# Cellular.net
KiCad netlist of a schematic drawn in Altium Designer
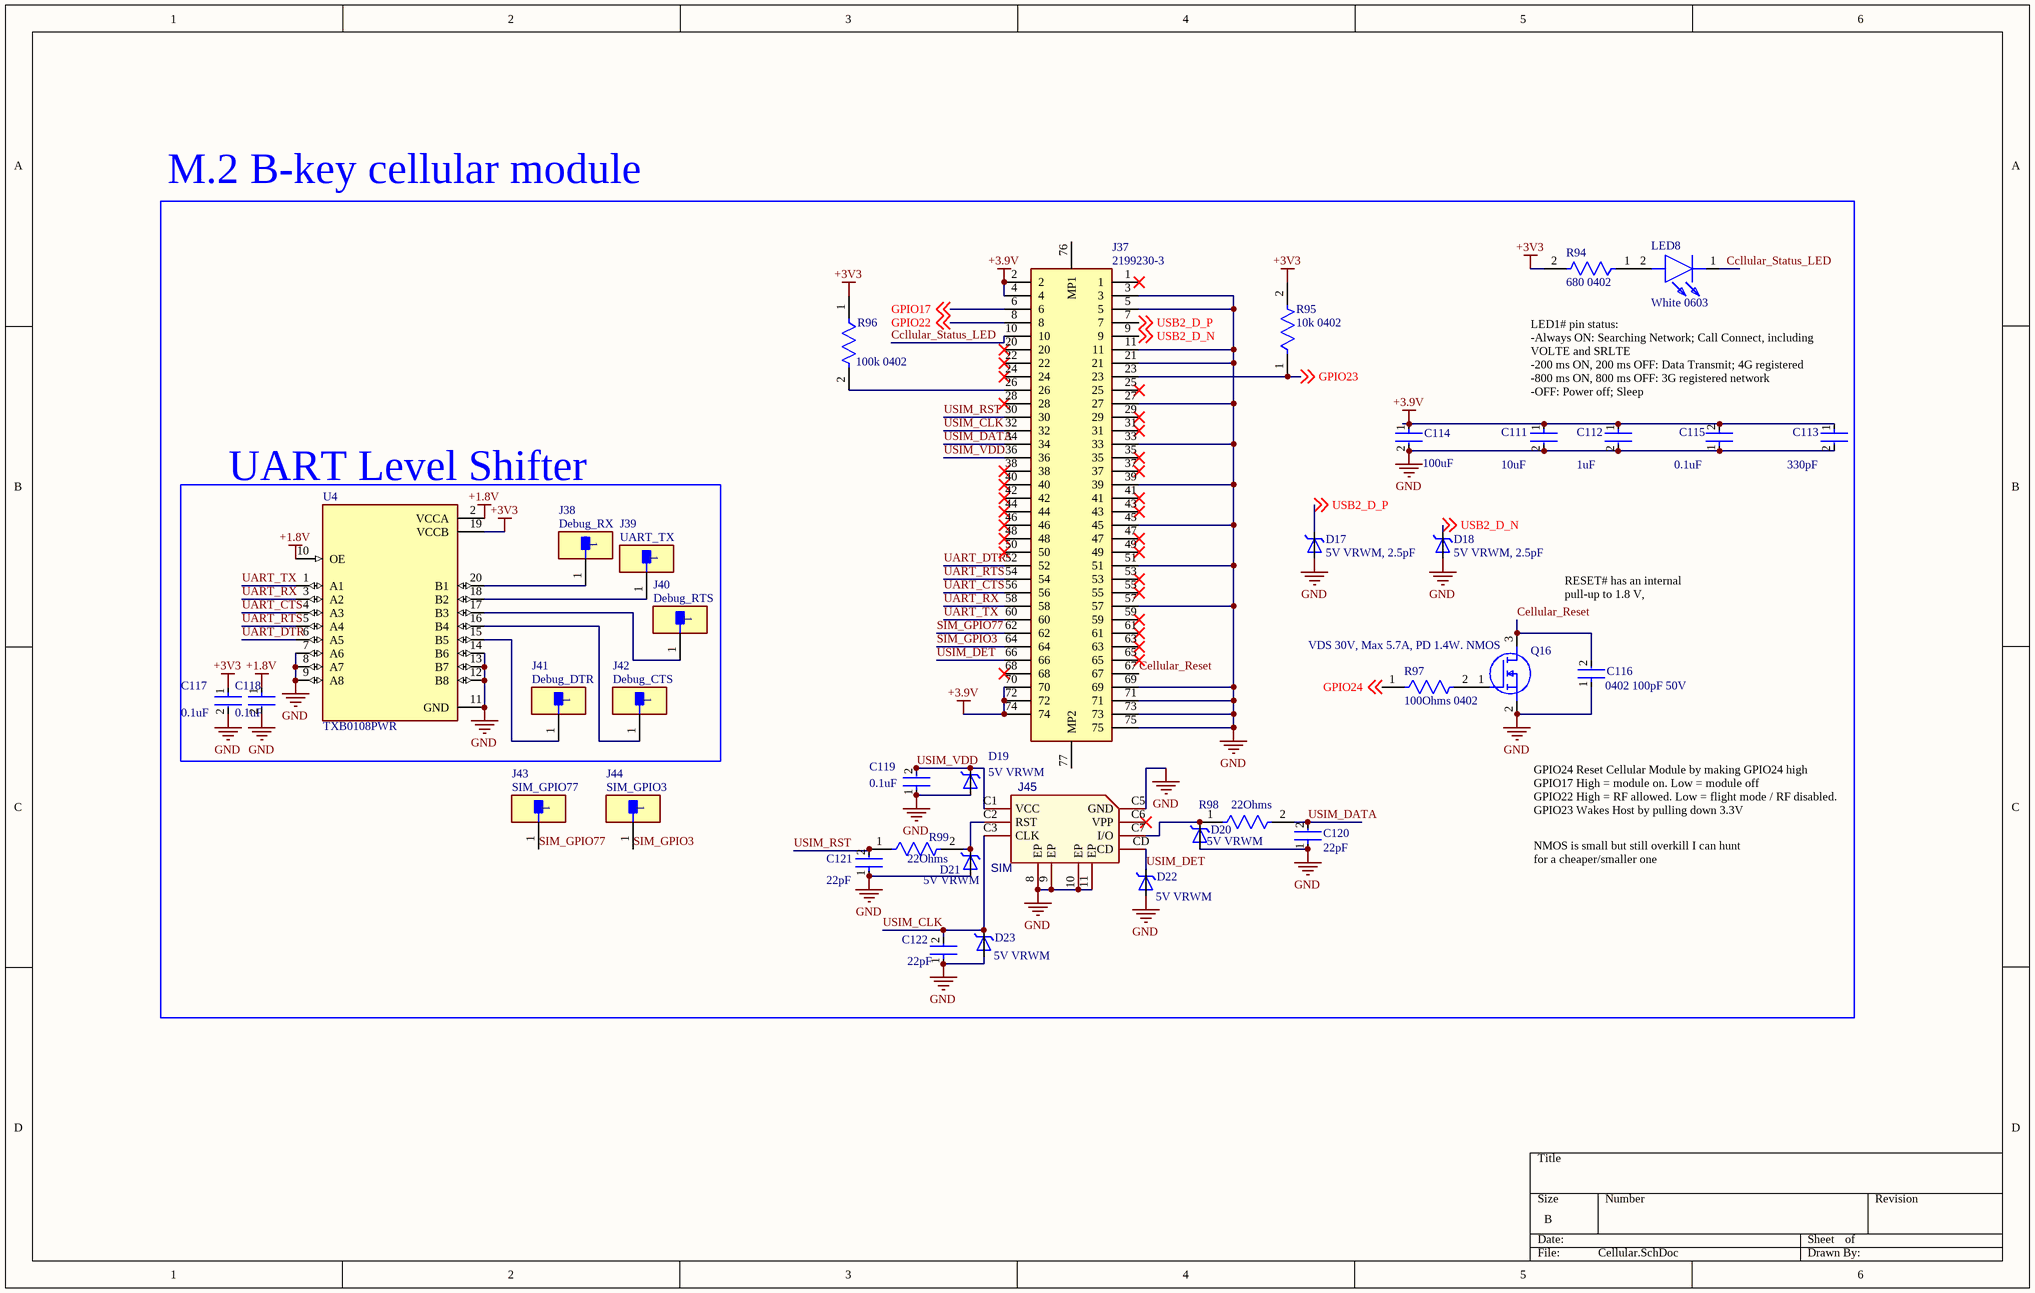
[diagram p0: Cellular.SchDoc]

(export (version "E")
  (design (tool "Eeschema 10.0.6"))
  (components
    (comp (ref "C111")
      (value "10uF")
      (footprint "FP-CC0603-DC-MFG")
      (description "C96446")
      (fields (field (name "TOLERANCE") "10%"))
      (libsource (lib "Altium Content Vault") (part "b4654b650e69147ec39a6b967a45e02"))
    )
    (comp (ref "C112")
      (value "1uF")
      (footprint "FP-C0402-BB-MFG")
      (description "C52923")
      (fields
        (field (name "TOLERANCE") "0.2")
        (field (name "OCTOPART") "https://octopart.com/c0402c104m3pac7867-kemet-84304880")
      )
      (libsource (lib "Altium Content Vault") (part "b4654b650e69147ec39a6b967a45e02"))
    )
    (comp (ref "C113")
      (value "330pF")
      (footprint "FP-C0402-BB-MFG")
      (description "C13533")
      (fields
        (field (name "TOLERANCE") "0.2")
        (field (name "OCTOPART") "https://octopart.com/c0402c104m3pac7867-kemet-84304880")
      )
      (libsource (lib "Altium Content Vault") (part "b4654b650e69147ec39a6b967a45e02"))
    )
    (comp (ref "C114")
      (value "100uF")
      (footprint "FP-CC1210-GD-IPC_A")
      (description "C7432790")
      (fields (field (name "TOLERANCE") "20%"))
      (libsource (lib "Altium Content Vault") (part "b4654b650e69147ec39a6b967a45e02"))
    )
    (comp (ref "C115")
      (value "0.1uF")
      (footprint "FP-C0402-BB-MFG")
      (description "C307331")
      (fields
        (field (name "TOLERANCE") "0.2")
        (field (name "OCTOPART") "https://octopart.com/c0402c104m3pac7867-kemet-84304880")
      )
      (libsource (lib "Altium Content Vault") (part "b4654b650e69147ec39a6b967a45e02"))
    )
    (comp (ref "C116")
      (value "0402 100pF 50V")
      (footprint "FP-C0402-BB-MFG")
      (description "C1546")
      (fields
        (field (name "TOLERANCE") "0.2")
        (field (name "OCTOPART") "https://octopart.com/c0402c104m3pac7867-kemet-84304880")
      )
      (libsource (lib "Altium Content Vault") (part "b4654b650e69147ec39a6b967a45e02"))
    )
    (comp (ref "C117")
      (value "0.1uF")
      (footprint "FP-C0402-BB-MFG")
      (description "C307331")
      (fields
        (field (name "TOLERANCE") "0.2")
        (field (name "OCTOPART") "https://octopart.com/c0402c104m3pac7867-kemet-84304880")
      )
      (libsource (lib "Altium Content Vault") (part "b4654b650e69147ec39a6b967a45e02"))
    )
    (comp (ref "C118")
      (value "0.1uF")
      (footprint "FP-C0402-BB-MFG")
      (description "C307331")
      (fields
        (field (name "TOLERANCE") "0.2")
        (field (name "OCTOPART") "https://octopart.com/c0402c104m3pac7867-kemet-84304880")
      )
      (libsource (lib "Altium Content Vault") (part "b4654b650e69147ec39a6b967a45e02"))
    )
    (comp (ref "C119")
      (value "0.1uF")
      (footprint "FP-C0402-BB-MFG")
      (description "C307331")
      (fields
        (field (name "TOLERANCE") "0.2")
        (field (name "OCTOPART") "https://octopart.com/c0402c104m3pac7867-kemet-84304880")
      )
      (libsource (lib "Altium Content Vault") (part "b4654b650e69147ec39a6b967a45e02"))
    )
    (comp (ref "C120")
      (value "22pF")
      (footprint "FP-C0402-BB-MFG")
      (description "C1555")
      (fields
        (field (name "TOLERANCE") "0.2")
        (field (name "OCTOPART") "https://octopart.com/c0402c104m3pac7867-kemet-84304880")
      )
      (libsource (lib "Altium Content Vault") (part "b4654b650e69147ec39a6b967a45e02"))
    )
    (comp (ref "C121")
      (value "22pF")
      (footprint "FP-C0402-BB-MFG")
      (description "C1555")
      (fields
        (field (name "TOLERANCE") "0.2")
        (field (name "OCTOPART") "https://octopart.com/c0402c104m3pac7867-kemet-84304880")
      )
      (libsource (lib "Altium Content Vault") (part "b4654b650e69147ec39a6b967a45e02"))
    )
    (comp (ref "C122")
      (value "22pF")
      (footprint "FP-C0402-BB-MFG")
      (description "C1555")
      (fields
        (field (name "TOLERANCE") "0.2")
        (field (name "OCTOPART") "https://octopart.com/c0402c104m3pac7867-kemet-84304880")
      )
      (libsource (lib "Altium Content Vault") (part "b4654b650e69147ec39a6b967a45e02"))
    )
    (comp (ref "D17")
      (value "5V VRWM, 2.5pF")
      (footprint "PcbLib1:SODFL1060X40N")
      (description "C242267")
      (fields (field (name "MF") "ON Semiconductor") (field (name "MP") "ESD9M5.0ST5G"))
      (libsource (lib "Schlib1") (part "ESD9M5.0ST5G"))
    )
    (comp (ref "D18")
      (value "5V VRWM, 2.5pF")
      (footprint "PcbLib1:SODFL1060X40N")
      (description "C242267")
      (fields (field (name "MF") "ON Semiconductor") (field (name "MP") "ESD9M5.0ST5G"))
      (libsource (lib "Schlib1") (part "ESD9M5.0ST5G"))
    )
    (comp (ref "D19")
      (value "5V VRWM")
      (footprint "PcbLib1:SODFL1060X40N")
      (description "C242267")
      (fields (field (name "MF") "ON Semiconductor") (field (name "MP") "ESD9M5.0ST5G"))
      (libsource (lib "Schlib1") (part "ESD9M5.0ST5G"))
    )
    (comp (ref "D20")
      (value "5V VRWM")
      (footprint "PcbLib1:SODFL1060X40N")
      (description "C242267")
      (fields (field (name "MF") "ON Semiconductor") (field (name "MP") "ESD9M5.0ST5G"))
      (libsource (lib "Schlib1") (part "ESD9M5.0ST5G"))
    )
    (comp (ref "D21")
      (value "5V VRWM")
      (footprint "PcbLib1:SODFL1060X40N")
      (description "C242267")
      (fields (field (name "MF") "ON Semiconductor") (field (name "MP") "ESD9M5.0ST5G"))
      (libsource (lib "Schlib1") (part "ESD9M5.0ST5G"))
    )
    (comp (ref "D22")
      (value "5V VRWM")
      (footprint "PcbLib1:SODFL1060X40N")
      (description "C242267")
      (fields (field (name "MF") "ON Semiconductor") (field (name "MP") "ESD9M5.0ST5G"))
      (libsource (lib "Schlib1") (part "ESD9M5.0ST5G"))
    )
    (comp (ref "D23")
      (value "5V VRWM")
      (footprint "PcbLib1:SODFL1060X40N")
      (description "C242267")
      (fields (field (name "MF") "ON Semiconductor") (field (name "MP") "ESD9M5.0ST5G"))
      (libsource (lib "Schlib1") (part "ESD9M5.0ST5G"))
    )
    (comp (ref "J37")
      (value "2199230-3")
      (footprint "PcbLib1:21992303")
      (description "C590859")
      (fields (field (name "MOUSER PART NUMBER") "571-2199230-3"))
      (libsource (lib "*") (part "2199230-3"))
    )
    (comp (ref "J38")
      (value "Debug_RX")
      (footprint "FP-5015-MFG")
      (description "PC TEST POINT MINIATURE")
      (fields (field (name "MANUFACTURER PART NUMBER") "5015") (field (name "MANUFACTURER") "keystone"))
      (libsource (lib "Altium Content Vault") (part "dd45045ce8184df9e99e12baf3f412c"))
    )
    (comp (ref "J39")
      (value "UART_TX")
      (footprint "FP-5015-MFG")
      (description "PC TEST POINT MINIATURE")
      (fields (field (name "MANUFACTURER PART NUMBER") "5015") (field (name "MANUFACTURER") "keystone"))
      (libsource (lib "Altium Content Vault") (part "dd45045ce8184df9e99e12baf3f412c"))
    )
    (comp (ref "J40")
      (value "Debug_RTS")
      (footprint "FP-5015-MFG")
      (description "PC TEST POINT MINIATURE")
      (fields (field (name "MANUFACTURER PART NUMBER") "5015") (field (name "MANUFACTURER") "keystone"))
      (libsource (lib "Altium Content Vault") (part "dd45045ce8184df9e99e12baf3f412c"))
    )
    (comp (ref "J41")
      (value "Debug_DTR")
      (footprint "FP-5015-MFG")
      (description "PC TEST POINT MINIATURE")
      (fields (field (name "MANUFACTURER PART NUMBER") "5015") (field (name "MANUFACTURER") "keystone"))
      (libsource (lib "Altium Content Vault") (part "dd45045ce8184df9e99e12baf3f412c"))
    )
    (comp (ref "J42")
      (value "Debug_CTS")
      (footprint "FP-5015-MFG")
      (description "PC TEST POINT MINIATURE")
      (fields (field (name "MANUFACTURER PART NUMBER") "5015") (field (name "MANUFACTURER") "keystone"))
      (libsource (lib "Altium Content Vault") (part "dd45045ce8184df9e99e12baf3f412c"))
    )
    (comp (ref "J43")
      (value "SIM_GPIO77")
      (footprint "FP-5015-MFG")
      (description "PC TEST POINT MINIATURE")
      (fields (field (name "MANUFACTURER PART NUMBER") "5015") (field (name "MANUFACTURER") "keystone"))
      (libsource (lib "Altium Content Vault") (part "dd45045ce8184df9e99e12baf3f412c"))
    )
    (comp (ref "J44")
      (value "SIM_GPIO3")
      (footprint "FP-5015-MFG")
      (description "PC TEST POINT MINIATURE")
      (fields (field (name "MANUFACTURER PART NUMBER") "5015") (field (name "MANUFACTURER") "keystone"))
      (libsource (lib "Altium Content Vault") (part "dd45045ce8184df9e99e12baf3f412c"))
    )
    (comp (ref "J45")
      (value "SIM")
      (footprint "PCBComponent_1")
      (description "C266888")
      (fields (field (name "MANUFACTURER") "XUNPU(讯普)") (field (name "MANUFACTURER PART") "SMN-303"))
      (libsource (lib "Schlib1") (part "SMN-303"))
    )
    (comp (ref "LED8")
      (value "White 0603")
      (footprint "SamacSys:LEDC1608X70N")
      (description "C2290")
      (fields (field (name "MANUFACTURER_PART_NUMBER") "KT-0603R"))
      (libsource (lib "*") (part "KT-0603R"))
    )
    (comp (ref "Q16")
      (value "VDS 30V, Max 5.7A, PD 1.4W. NMOS")
      (footprint "PcbLib1:SOT95P280X125-3N")
      (description "C20917")
      (fields (field (name "MANUFACTURER_PART_NUMBER") "AO3400A"))
      (libsource (lib "*") (part "AO3400A"))
    )
    (comp (ref "R94")
      (value "680 0402")
      (footprint "FP-AF0402-IPC_B")
      (description "C2835749")
      (fields (field (name "TOLERANCE") "5%"))
      (libsource (lib "Altium Content Vault") (part "1029c3af85768c4190bb7ad29bc67b5"))
    )
    (comp (ref "R95")
      (value "10k 0402")
      (footprint "FP-RMCF0402-MFG")
      (description "C25744")
      (fields (field (name "TOLERANCE") "5%"))
      (libsource (lib "Altium Content Vault") (part "1029c3af85768c4190bb7ad29bc67b5"))
    )
    (comp (ref "R96")
      (value "100k 0402")
      (footprint "FP-RMCF0402-MFG")
      (description "C25741")
      (fields (field (name "TOLERANCE") "5%"))
      (libsource (lib "Altium Content Vault") (part "1029c3af85768c4190bb7ad29bc67b5"))
    )
    (comp (ref "R97")
      (value "100Ohms 0402")
      (footprint "FP-RMCF0402-MFG")
      (description "C25076")
      (fields (field (name "TOLERANCE") "5%"))
      (libsource (lib "Altium Content Vault") (part "1029c3af85768c4190bb7ad29bc67b5"))
    )
    (comp (ref "R98")
      (value "22Ohms")
      (footprint "FP-RMCF0402-MFG")
      (description "C25092")
      (fields (field (name "TOLERANCE") "5%"))
      (libsource (lib "Altium Content Vault") (part "1029c3af85768c4190bb7ad29bc67b5"))
    )
    (comp (ref "R99")
      (value "22Ohms")
      (footprint "FP-RMCF0402-MFG")
      (description "C25092")
      (fields (field (name "TOLERANCE") "5%"))
      (libsource (lib "Altium Content Vault") (part "1029c3af85768c4190bb7ad29bc67b5"))
    )
    (comp (ref "U4")
      (value "TXB0108PWR")
      (footprint "SOP65P640X120-20N")
      (description "C53406")
      (fields (field (name "MF") "Texas Instruments") (field (name "DIGI-KEY_PART_NUMBER") "296-21527-2-ND"))
      (libsource (lib "Schlib1") (part "TXB0108PWR"))
    )
  )
  (nets
    (net (code "1") (name "+1.8V") (class "Default")
      (node (ref "C118") (pin "1") (pinfunction "1_1") (pintype "passive"))
      (node (ref "U4") (pin "10") (pinfunction "OE_10") (pintype "input"))
      (node (ref "U4") (pin "2") (pinfunction "VCCA_2") (pintype "power_in"))
    )
    (net (code "2") (name "+3.9V") (class "Default")
      (node (ref "C111") (pin "1") (pinfunction "1_1") (pintype "passive"))
      (node (ref "C112") (pin "1") (pinfunction "1_1") (pintype "passive"))
      (node (ref "C113") (pin "1") (pinfunction "1_1") (pintype "passive"))
      (node (ref "C114") (pin "1") (pinfunction "1_1") (pintype "passive"))
      (node (ref "C115") (pin "2") (pinfunction "2_2") (pintype "passive"))
      (node (ref "J37") (pin "2") (pinfunction "2_2") (pintype "passive"))
      (node (ref "J37") (pin "4") (pinfunction "4_4") (pintype "passive"))
      (node (ref "J37") (pin "70") (pinfunction "70_70") (pintype "passive"))
      (node (ref "J37") (pin "72") (pinfunction "72_72") (pintype "passive"))
      (node (ref "J37") (pin "74") (pinfunction "74_74") (pintype "passive"))
    )
    (net (code "3") (name "+3V3") (class "Default")
      (node (ref "C117") (pin "1") (pinfunction "1_1") (pintype "passive"))
      (node (ref "R94") (pin "2") (pinfunction "2_2") (pintype "passive"))
      (node (ref "R95") (pin "2") (pinfunction "2_2") (pintype "passive"))
      (node (ref "R96") (pin "1") (pinfunction "1_1") (pintype "passive"))
      (node (ref "U4") (pin "19") (pinfunction "VCCB_19") (pintype "power_in"))
    )
    (net (code "4") (name "/Ccllular_Status_LED") (class "Default")
      (node (ref "J37") (pin "10") (pinfunction "10_10") (pintype "passive"))
      (node (ref "LED8") (pin "1") (pinfunction "K_1") (pintype "passive"))
    )
    (net (code "5") (name "/Cellular_Reset") (class "Default")
      (node (ref "C116") (pin "2") (pinfunction "2_2") (pintype "passive"))
      (node (ref "J37") (pin "67") (pinfunction "67_67") (pintype "passive"))
      (node (ref "Q16") (pin "3") (pinfunction "D_3") (pintype "passive"))
    )
    (net (code "6") (name "/SIM_GPIO3") (class "Default")
      (node (ref "J37") (pin "64") (pinfunction "64_64") (pintype "passive"))
      (node (ref "J44") (pin "1") (pinfunction "1_1") (pintype "passive"))
    )
    (net (code "7") (name "/SIM_GPIO77") (class "Default")
      (node (ref "J37") (pin "62") (pinfunction "62_62") (pintype "passive"))
      (node (ref "J43") (pin "1") (pinfunction "1_1") (pintype "passive"))
    )
    (net (code "8") (name "/UART_CTS") (class "Default")
      (node (ref "J37") (pin "56") (pinfunction "56_56") (pintype "passive"))
      (node (ref "U4") (pin "4") (pinfunction "A3_4") (pintype "bidirectional"))
    )
    (net (code "9") (name "/UART_DTR") (class "Default")
      (node (ref "J37") (pin "52") (pinfunction "52_52") (pintype "passive"))
      (node (ref "U4") (pin "6") (pinfunction "A5_6") (pintype "bidirectional"))
    )
    (net (code "10") (name "/UART_RTS") (class "Default")
      (node (ref "J37") (pin "54") (pinfunction "54_54") (pintype "passive"))
      (node (ref "U4") (pin "5") (pinfunction "A4_5") (pintype "bidirectional"))
    )
    (net (code "11") (name "/UART_RX") (class "Default")
      (node (ref "J37") (pin "58") (pinfunction "58_58") (pintype "passive"))
      (node (ref "U4") (pin "3") (pinfunction "A2_3") (pintype "bidirectional"))
    )
    (net (code "12") (name "/UART_TX") (class "Default")
      (node (ref "J37") (pin "60") (pinfunction "60_60") (pintype "passive"))
      (node (ref "U4") (pin "1") (pinfunction "A1_1") (pintype "bidirectional"))
    )
    (net (code "13") (name "/USIM_CLK") (class "Default")
      (node (ref "C122") (pin "2") (pinfunction "2_2") (pintype "passive"))
      (node (ref "D23") (pin "1") (pinfunction "1_1") (pintype "passive"))
      (node (ref "J37") (pin "32") (pinfunction "32_32") (pintype "passive"))
      (node (ref "J45") (pin "C3") (pinfunction "CLK_C3") (pintype "passive"))
    )
    (net (code "14") (name "/USIM_DATA") (class "Default")
      (node (ref "C120") (pin "2") (pinfunction "2_2") (pintype "passive"))
      (node (ref "J37") (pin "34") (pinfunction "34_34") (pintype "passive"))
      (node (ref "R98") (pin "2") (pinfunction "2_2") (pintype "passive"))
    )
    (net (code "15") (name "/USIM_DET") (class "Default")
      (node (ref "D22") (pin "1") (pinfunction "1_1") (pintype "passive"))
      (node (ref "J37") (pin "66") (pinfunction "66_66") (pintype "passive"))
      (node (ref "J45") (pin "CD") (pinfunction "CD_CD") (pintype "passive"))
    )
    (net (code "16") (name "/USIM_RST") (class "Default")
      (node (ref "C121") (pin "2") (pinfunction "2_2") (pintype "passive"))
      (node (ref "J37") (pin "30") (pinfunction "30_30") (pintype "passive"))
      (node (ref "R99") (pin "1") (pinfunction "1_1") (pintype "passive"))
    )
    (net (code "17") (name "/USIM_VDD") (class "Default")
      (node (ref "C119") (pin "2") (pinfunction "2_2") (pintype "passive"))
      (node (ref "D19") (pin "1") (pinfunction "1_1") (pintype "passive"))
      (node (ref "J37") (pin "36") (pinfunction "36_36") (pintype "passive"))
      (node (ref "J45") (pin "C1") (pinfunction "VCC_C1") (pintype "passive"))
    )
    (net (code "18") (name "GND") (class "Default")
      (node (ref "C111") (pin "2") (pinfunction "2_2") (pintype "passive"))
      (node (ref "C112") (pin "2") (pinfunction "2_2") (pintype "passive"))
      (node (ref "C113") (pin "2") (pinfunction "2_2") (pintype "passive"))
      (node (ref "C114") (pin "2") (pinfunction "2_2") (pintype "passive"))
      (node (ref "C115") (pin "1") (pinfunction "1_1") (pintype "passive"))
      (node (ref "C116") (pin "1") (pinfunction "1_1") (pintype "passive"))
      (node (ref "C117") (pin "2") (pinfunction "2_2") (pintype "passive"))
      (node (ref "C118") (pin "2") (pinfunction "2_2") (pintype "passive"))
      (node (ref "C119") (pin "1") (pinfunction "1_1") (pintype "passive"))
      (node (ref "C120") (pin "1") (pinfunction "1_1") (pintype "passive"))
      (node (ref "C121") (pin "1") (pinfunction "1_1") (pintype "passive"))
      (node (ref "C122") (pin "1") (pinfunction "1_1") (pintype "passive"))
      (node (ref "D17") (pin "2") (pinfunction "2_2") (pintype "passive"))
      (node (ref "D18") (pin "2") (pinfunction "2_2") (pintype "passive"))
      (node (ref "D19") (pin "2") (pinfunction "2_2") (pintype "passive"))
      (node (ref "D20") (pin "2") (pinfunction "2_2") (pintype "passive"))
      (node (ref "D21") (pin "2") (pinfunction "2_2") (pintype "passive"))
      (node (ref "D22") (pin "2") (pinfunction "2_2") (pintype "passive"))
      (node (ref "D23") (pin "2") (pinfunction "2_2") (pintype "passive"))
      (node (ref "J37") (pin "11") (pinfunction "11_11") (pintype "passive"))
      (node (ref "J37") (pin "21") (pinfunction "21_21") (pintype "passive"))
      (node (ref "J37") (pin "27") (pinfunction "27_27") (pintype "passive"))
      (node (ref "J37") (pin "3") (pinfunction "3_3") (pintype "passive"))
      (node (ref "J37") (pin "33") (pinfunction "33_33") (pintype "passive"))
      (node (ref "J37") (pin "39") (pinfunction "39_39") (pintype "passive"))
      (node (ref "J37") (pin "45") (pinfunction "45_45") (pintype "passive"))
      (node (ref "J37") (pin "5") (pinfunction "5_5") (pintype "passive"))
      (node (ref "J37") (pin "51") (pinfunction "51_51") (pintype "passive"))
      (node (ref "J37") (pin "57") (pinfunction "57_57") (pintype "passive"))
      (node (ref "J37") (pin "69") (pinfunction "69_69") (pintype "passive"))
      (node (ref "J37") (pin "71") (pinfunction "71_71") (pintype "passive"))
      (node (ref "J37") (pin "73") (pinfunction "73_73") (pintype "passive"))
      (node (ref "J37") (pin "75") (pinfunction "75_75") (pintype "passive"))
      (node (ref "J45") (pin "10") (pinfunction "EP_10") (pintype "passive"))
      (node (ref "J45") (pin "11") (pinfunction "EP_11") (pintype "passive"))
      (node (ref "J45") (pin "8") (pinfunction "EP_8") (pintype "passive"))
      (node (ref "J45") (pin "9") (pinfunction "EP_9") (pintype "passive"))
      (node (ref "J45") (pin "C5") (pinfunction "GND_C5") (pintype "passive"))
      (node (ref "Q16") (pin "2") (pinfunction "S_2") (pintype "passive"))
      (node (ref "U4") (pin "11") (pinfunction "GND_11") (pintype "power_in"))
      (node (ref "U4") (pin "12") (pinfunction "B8_12") (pintype "bidirectional"))
      (node (ref "U4") (pin "13") (pinfunction "B7_13") (pintype "bidirectional"))
      (node (ref "U4") (pin "14") (pinfunction "B6_14") (pintype "bidirectional"))
      (node (ref "U4") (pin "7") (pinfunction "A6_7") (pintype "bidirectional"))
      (node (ref "U4") (pin "8") (pinfunction "A7_8") (pintype "bidirectional"))
      (node (ref "U4") (pin "9") (pinfunction "A8_9") (pintype "bidirectional"))
    )
    (net (code "19") (name "GPIO17") (class "Default")
      (node (ref "J37") (pin "6") (pinfunction "6_6") (pintype "passive"))
    )
    (net (code "20") (name "GPIO22") (class "Default")
      (node (ref "J37") (pin "8") (pinfunction "8_8") (pintype "passive"))
    )
    (net (code "21") (name "GPIO23") (class "Default")
      (node (ref "J37") (pin "23") (pinfunction "23_23") (pintype "passive"))
      (node (ref "R95") (pin "1") (pinfunction "1_1") (pintype "passive"))
    )
    (net (code "22") (name "GPIO24") (class "Default")
      (node (ref "R97") (pin "1") (pinfunction "1_1") (pintype "passive"))
    )
    (net (code "23") (name "Net-(J37-Pad26)") (class "Default")
      (node (ref "J37") (pin "26") (pinfunction "26_26") (pintype "passive"))
      (node (ref "R96") (pin "2") (pinfunction "2_2") (pintype "passive"))
    )
    (net (code "24") (name "Net-(J45-I{slash}O)") (class "Default")
      (node (ref "D20") (pin "1") (pinfunction "1_1") (pintype "passive"))
      (node (ref "J45") (pin "C7") (pinfunction "I/O_C7") (pintype "passive"))
      (node (ref "R98") (pin "1") (pinfunction "1_1") (pintype "passive"))
    )
    (net (code "25") (name "Net-(J45-RST)") (class "Default")
      (node (ref "D21") (pin "1") (pinfunction "1_1") (pintype "passive"))
      (node (ref "J45") (pin "C2") (pinfunction "RST_C2") (pintype "passive"))
      (node (ref "R99") (pin "2") (pinfunction "2_2") (pintype "passive"))
    )
    (net (code "26") (name "Net-(LED8-A)") (class "Default")
      (node (ref "LED8") (pin "2") (pinfunction "A_2") (pintype "passive"))
      (node (ref "R94") (pin "1") (pinfunction "1_1") (pintype "passive"))
    )
    (net (code "27") (name "Net-(Q16-G)") (class "Default")
      (node (ref "Q16") (pin "1") (pinfunction "G_1") (pintype "passive"))
      (node (ref "R97") (pin "2") (pinfunction "2_2") (pintype "passive"))
    )
    (net (code "28") (name "Net-(U4-B1)") (class "Default")
      (node (ref "J38") (pin "1") (pinfunction "1_1") (pintype "passive"))
      (node (ref "U4") (pin "20") (pinfunction "B1_20") (pintype "bidirectional"))
    )
    (net (code "29") (name "Net-(U4-B2)") (class "Default")
      (node (ref "J39") (pin "1") (pinfunction "1_1") (pintype "passive"))
      (node (ref "U4") (pin "18") (pinfunction "B2_18") (pintype "bidirectional"))
    )
    (net (code "30") (name "Net-(U4-B3)") (class "Default")
      (node (ref "J40") (pin "1") (pinfunction "1_1") (pintype "passive"))
      (node (ref "U4") (pin "17") (pinfunction "B3_17") (pintype "bidirectional"))
    )
    (net (code "31") (name "Net-(U4-B4)") (class "Default")
      (node (ref "J42") (pin "1") (pinfunction "1_1") (pintype "passive"))
      (node (ref "U4") (pin "16") (pinfunction "B4_16") (pintype "bidirectional"))
    )
    (net (code "32") (name "Net-(U4-B5)") (class "Default")
      (node (ref "J41") (pin "1") (pinfunction "1_1") (pintype "passive"))
      (node (ref "U4") (pin "15") (pinfunction "B5_15") (pintype "bidirectional"))
    )
    (net (code "33") (name "USB2_D_N") (class "Default")
      (node (ref "D18") (pin "1") (pinfunction "1_1") (pintype "passive"))
      (node (ref "J37") (pin "9") (pinfunction "9_9") (pintype "passive"))
    )
    (net (code "34") (name "USB2_D_P") (class "Default")
      (node (ref "D17") (pin "1") (pinfunction "1_1") (pintype "passive"))
      (node (ref "J37") (pin "7") (pinfunction "7_7") (pintype "passive"))
    )
    (net (code "35") (name "unconnected-(J37-MP1-Pad76)") (class "Default")
      (node (ref "J37") (pin "76") (pinfunction "MP1_76") (pintype "passive"))
    )
    (net (code "36") (name "unconnected-(J37-MP2-Pad77)") (class "Default")
      (node (ref "J37") (pin "77") (pinfunction "MP2_77") (pintype "passive"))
    )
    (net (code "37") (name "unconnected-(J37-Pad1)") (class "Default")
      (node (ref "J37") (pin "1") (pinfunction "1_1") (pintype "passive+no_connect"))
    )
    (net (code "38") (name "unconnected-(J37-Pad20)") (class "Default")
      (node (ref "J37") (pin "20") (pinfunction "20_20") (pintype "passive+no_connect"))
    )
    (net (code "39") (name "unconnected-(J37-Pad22)") (class "Default")
      (node (ref "J37") (pin "22") (pinfunction "22_22") (pintype "passive+no_connect"))
    )
    (net (code "40") (name "unconnected-(J37-Pad24)") (class "Default")
      (node (ref "J37") (pin "24") (pinfunction "24_24") (pintype "passive+no_connect"))
    )
    (net (code "41") (name "unconnected-(J37-Pad25)") (class "Default")
      (node (ref "J37") (pin "25") (pinfunction "25_25") (pintype "passive+no_connect"))
    )
    (net (code "42") (name "unconnected-(J37-Pad28)") (class "Default")
      (node (ref "J37") (pin "28") (pinfunction "28_28") (pintype "passive+no_connect"))
    )
    (net (code "43") (name "unconnected-(J37-Pad29)") (class "Default")
      (node (ref "J37") (pin "29") (pinfunction "29_29") (pintype "passive+no_connect"))
    )
    (net (code "44") (name "unconnected-(J37-Pad31)") (class "Default")
      (node (ref "J37") (pin "31") (pinfunction "31_31") (pintype "passive+no_connect"))
    )
    (net (code "45") (name "unconnected-(J37-Pad35)") (class "Default")
      (node (ref "J37") (pin "35") (pinfunction "35_35") (pintype "passive+no_connect"))
    )
    (net (code "46") (name "unconnected-(J37-Pad37)") (class "Default")
      (node (ref "J37") (pin "37") (pinfunction "37_37") (pintype "passive+no_connect"))
    )
    (net (code "47") (name "unconnected-(J37-Pad38)") (class "Default")
      (node (ref "J37") (pin "38") (pinfunction "38_38") (pintype "passive+no_connect"))
    )
    (net (code "48") (name "unconnected-(J37-Pad40)") (class "Default")
      (node (ref "J37") (pin "40") (pinfunction "40_40") (pintype "passive+no_connect"))
    )
    (net (code "49") (name "unconnected-(J37-Pad41)") (class "Default")
      (node (ref "J37") (pin "41") (pinfunction "41_41") (pintype "passive+no_connect"))
    )
    (net (code "50") (name "unconnected-(J37-Pad42)") (class "Default")
      (node (ref "J37") (pin "42") (pinfunction "42_42") (pintype "passive+no_connect"))
    )
    (net (code "51") (name "unconnected-(J37-Pad43)") (class "Default")
      (node (ref "J37") (pin "43") (pinfunction "43_43") (pintype "passive+no_connect"))
    )
    (net (code "52") (name "unconnected-(J37-Pad44)") (class "Default")
      (node (ref "J37") (pin "44") (pinfunction "44_44") (pintype "passive+no_connect"))
    )
    (net (code "53") (name "unconnected-(J37-Pad46)") (class "Default")
      (node (ref "J37") (pin "46") (pinfunction "46_46") (pintype "passive+no_connect"))
    )
    (net (code "54") (name "unconnected-(J37-Pad47)") (class "Default")
      (node (ref "J37") (pin "47") (pinfunction "47_47") (pintype "passive+no_connect"))
    )
    (net (code "55") (name "unconnected-(J37-Pad48)") (class "Default")
      (node (ref "J37") (pin "48") (pinfunction "48_48") (pintype "passive+no_connect"))
    )
    (net (code "56") (name "unconnected-(J37-Pad49)") (class "Default")
      (node (ref "J37") (pin "49") (pinfunction "49_49") (pintype "passive+no_connect"))
    )
    (net (code "57") (name "unconnected-(J37-Pad50)") (class "Default")
      (node (ref "J37") (pin "50") (pinfunction "50_50") (pintype "passive+no_connect"))
    )
    (net (code "58") (name "unconnected-(J37-Pad53)") (class "Default")
      (node (ref "J37") (pin "53") (pinfunction "53_53") (pintype "passive+no_connect"))
    )
    (net (code "59") (name "unconnected-(J37-Pad55)") (class "Default")
      (node (ref "J37") (pin "55") (pinfunction "55_55") (pintype "passive+no_connect"))
    )
    (net (code "60") (name "unconnected-(J37-Pad59)") (class "Default")
      (node (ref "J37") (pin "59") (pinfunction "59_59") (pintype "passive+no_connect"))
    )
    (net (code "61") (name "unconnected-(J37-Pad61)") (class "Default")
      (node (ref "J37") (pin "61") (pinfunction "61_61") (pintype "passive+no_connect"))
    )
    (net (code "62") (name "unconnected-(J37-Pad63)") (class "Default")
      (node (ref "J37") (pin "63") (pinfunction "63_63") (pintype "passive+no_connect"))
    )
    (net (code "63") (name "unconnected-(J37-Pad65)") (class "Default")
      (node (ref "J37") (pin "65") (pinfunction "65_65") (pintype "passive+no_connect"))
    )
    (net (code "64") (name "unconnected-(J37-Pad68)") (class "Default")
      (node (ref "J37") (pin "68") (pinfunction "68_68") (pintype "passive+no_connect"))
    )
    (net (code "65") (name "unconnected-(J45-VPP-PadC6)") (class "Default")
      (node (ref "J45") (pin "C6") (pinfunction "VPP_C6") (pintype "passive+no_connect"))
    )
  )
)
